# front_io.net
KiCad netlist of a schematic drawn in Altium Designer
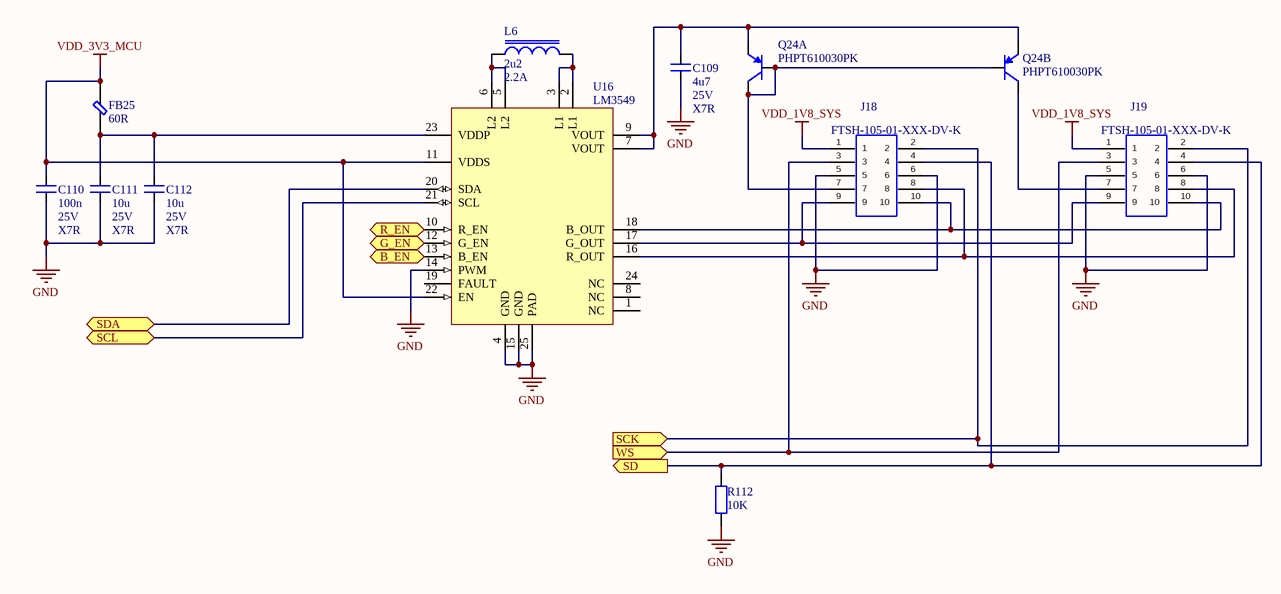
[diagram p0: front_io.SchDoc]

(export (version "E")
  (design (tool "Eeschema 10.0.6"))
  (components
    (comp (ref "C109")
      (value "4u7")
      (footprint "C3216[1206]")
      (description "Capacitor")
      (fields (field (name "VOLTAGE") "25V") (field (name "TYPE") "X7R") (field (name "Comment") "cap"))
      (libsource (lib "gpa_passives") (part "cap"))
    )
    (comp (ref "C110")
      (value "100n")
      (footprint "C1005[0402]")
      (description "Capacitor")
      (fields (field (name "VOLTAGE") "25V") (field (name "TYPE") "X7R") (field (name "Comment") "cap"))
      (libsource (lib "gpa_passives") (part "cap"))
    )
    (comp (ref "C111")
      (value "10u")
      (footprint "C3216[1206]")
      (description "Capacitor")
      (fields (field (name "VOLTAGE") "25V") (field (name "TYPE") "X7R") (field (name "Comment") "cap"))
      (libsource (lib "gpa_passives") (part "cap"))
    )
    (comp (ref "C112")
      (value "10u")
      (footprint "C3216[1206]")
      (description "Capacitor")
      (fields (field (name "VOLTAGE") "25V") (field (name "TYPE") "X7R") (field (name "Comment") "cap"))
      (libsource (lib "gpa_passives") (part "cap"))
    )
    (comp (ref "FB25")
      (value "60R")
      (footprint "FBC1608X07N")
      (description "Ferrite bead")
      (libsource (lib "gpa_passives") (part "ferrite_bead"))
    )
    (comp (ref "J18")
      (value "FTSH-105-01-XXX-DV-K")
      (footprint "FTSH-105-01-XXX-DV-K")
      (description "TERMINAL STRIP, .050\"(1.27mm) PITCH, 10 PINS, KEYED")
      (fields (field (name "MANUFACTURER") "SAMTEC") (field (name "CREATED") "November 30, 2016 - Wendy Xin"))
      (libsource (lib "FTSH-105-01-XXX-DV-K") (part "FTSH-105-01-XXX-DV-K"))
    )
    (comp (ref "J19")
      (value "FTSH-105-01-XXX-DV-K")
      (footprint "FTSH-105-01-XXX-DV-K")
      (description "TERMINAL STRIP, .050\"(1.27mm) PITCH, 10 PINS, KEYED")
      (fields (field (name "MANUFACTURER") "SAMTEC") (field (name "CREATED") "November 30, 2016 - Wendy Xin"))
      (libsource (lib "FTSH-105-01-XXX-DV-K") (part "FTSH-105-01-XXX-DV-K"))
    )
    (comp (ref "L6")
      (value "2u2")
      (footprint "YUDEN_NRS4018T-XXXMDGJ")
      (fields (field (name "CURRENT") "2.2A") (field (name "Comment") "ASPI-0630LR-XXXM-T15"))
      (libsource (lib "gpa_passives") (part "ind"))
    )
    (comp (ref "Q24")
      (value "PHPT610030PK")
      (footprint "NXP_LFPAK56D127P610X105-8N")
      (description "PNP Bipolar Transistor")
      (fields (field (name "PUBLISHER") "Altium Limited"))
      (libsource (lib "gpa_actives") (part "pnp_bipolar_dual"))
    )
    (comp (ref "R112")
      (value "10K")
      (footprint "R1005[0402]")
      (description "Resistor")
      (fields (field (name "TOLERANCE") "5%") (field (name "Comment") "res"))
      (libsource (lib "gpa_passives") (part "res"))
    )
    (comp (ref "U16")
      (value "LM3549")
      (footprint "TI_QFN50P400X400X80_HS-25M")
      (libsource (lib "gpa_ti") (part "lm3549"))
    )
  )
  (nets
    (net (code "1") (name "/B_EN") (class "Default")
      (node (ref "U16") (pin "13") (pinfunction "B_EN_13") (pintype "input"))
    )
    (net (code "2") (name "/G_EN") (class "Default")
      (node (ref "U16") (pin "12") (pinfunction "G_EN_12") (pintype "input"))
    )
    (net (code "3") (name "/R_EN") (class "Default")
      (node (ref "U16") (pin "10") (pinfunction "R_EN_10") (pintype "input"))
    )
    (net (code "4") (name "/SCK") (class "Default")
      (node (ref "J18") (pin "2") (pinfunction "2_2") (pintype "passive"))
      (node (ref "J19") (pin "2") (pinfunction "2_2") (pintype "passive"))
    )
    (net (code "5") (name "/SCL") (class "Default")
      (node (ref "U16") (pin "21") (pinfunction "SCL_21") (pintype "bidirectional"))
    )
    (net (code "6") (name "/SD") (class "Default")
      (node (ref "J18") (pin "4") (pinfunction "4_4") (pintype "passive"))
      (node (ref "J19") (pin "4") (pinfunction "4_4") (pintype "passive"))
      (node (ref "R112") (pin "2") (pinfunction "2_2") (pintype "passive"))
    )
    (net (code "7") (name "/SDA") (class "Default")
      (node (ref "U16") (pin "20") (pinfunction "SDA_20") (pintype "bidirectional"))
    )
    (net (code "8") (name "/WS") (class "Default")
      (node (ref "J18") (pin "3") (pinfunction "3_3") (pintype "passive"))
      (node (ref "J19") (pin "3") (pinfunction "3_3") (pintype "passive"))
    )
    (net (code "9") (name "GND") (class "Default")
      (node (ref "C109") (pin "1") (pinfunction "1_1") (pintype "passive"))
      (node (ref "C110") (pin "1") (pinfunction "1_1") (pintype "passive"))
      (node (ref "C111") (pin "1") (pinfunction "1_1") (pintype "passive"))
      (node (ref "C112") (pin "1") (pinfunction "1_1") (pintype "passive"))
      (node (ref "J18") (pin "5") (pinfunction "5_5") (pintype "passive"))
      (node (ref "J18") (pin "6") (pinfunction "6_6") (pintype "passive"))
      (node (ref "J19") (pin "5") (pinfunction "5_5") (pintype "passive"))
      (node (ref "J19") (pin "6") (pinfunction "6_6") (pintype "passive"))
      (node (ref "R112") (pin "1") (pinfunction "1_1") (pintype "passive"))
      (node (ref "U16") (pin "14") (pinfunction "PWM_14") (pintype "input"))
      (node (ref "U16") (pin "15") (pinfunction "GND_15") (pintype "power_in"))
      (node (ref "U16") (pin "25") (pinfunction "PAD_25") (pintype "power_in"))
      (node (ref "U16") (pin "4") (pinfunction "GND_4") (pintype "power_in"))
    )
    (net (code "10") (name "Net-(C109-Pad2)") (class "Default")
      (node (ref "C109") (pin "2") (pinfunction "2_2") (pintype "passive"))
      (node (ref "Q24") (pin "E1") (pinfunction "E1_E1") (pintype "passive"))
      (node (ref "Q24") (pin "E2") (pinfunction "E2_E2") (pintype "passive"))
      (node (ref "U16") (pin "7") (pinfunction "VOUT_7") (pintype "power_in"))
      (node (ref "U16") (pin "9") (pinfunction "VOUT_9") (pintype "power_in"))
    )
    (net (code "11") (name "Net-(J18-Pad7)") (class "Default")
      (node (ref "J18") (pin "7") (pinfunction "7_7") (pintype "passive"))
      (node (ref "Q24") (pin "B1") (pinfunction "B1_B1") (pintype "passive"))
      (node (ref "Q24") (pin "B2") (pinfunction "B2_B2") (pintype "passive"))
      (node (ref "Q24") (pin "C1") (pinfunction "C1_C1") (pintype "passive"))
    )
    (net (code "12") (name "Net-(J19-Pad7)") (class "Default")
      (node (ref "J19") (pin "7") (pinfunction "7_7") (pintype "passive"))
      (node (ref "Q24") (pin "C2") (pinfunction "C2_C2") (pintype "passive"))
    )
    (net (code "13") (name "Net-(L6-Pad1)") (class "Default")
      (node (ref "L6") (pin "1") (pinfunction "1_1") (pintype "passive"))
      (node (ref "U16") (pin "5") (pinfunction "L2_5") (pintype "power_in"))
      (node (ref "U16") (pin "6") (pinfunction "L2_6") (pintype "power_in"))
    )
    (net (code "14") (name "Net-(L6-Pad2)") (class "Default")
      (node (ref "L6") (pin "2") (pinfunction "2_2") (pintype "passive"))
      (node (ref "U16") (pin "2") (pinfunction "L1_2") (pintype "power_in"))
      (node (ref "U16") (pin "3") (pinfunction "L1_3") (pintype "power_in"))
    )
    (net (code "15") (name "Net-(U16-B_OUT)") (class "Default")
      (node (ref "J18") (pin "10") (pinfunction "10_10") (pintype "passive"))
      (node (ref "J19") (pin "10") (pinfunction "10_10") (pintype "passive"))
      (node (ref "U16") (pin "18") (pinfunction "B_OUT_18") (pintype "open_emitter"))
    )
    (net (code "16") (name "Net-(U16-G_OUT)") (class "Default")
      (node (ref "J18") (pin "9") (pinfunction "9_9") (pintype "passive"))
      (node (ref "J19") (pin "9") (pinfunction "9_9") (pintype "passive"))
      (node (ref "U16") (pin "17") (pinfunction "G_OUT_17") (pintype "open_emitter"))
    )
    (net (code "17") (name "Net-(U16-R_OUT)") (class "Default")
      (node (ref "J18") (pin "8") (pinfunction "8_8") (pintype "passive"))
      (node (ref "J19") (pin "8") (pinfunction "8_8") (pintype "passive"))
      (node (ref "U16") (pin "16") (pinfunction "R_OUT_16") (pintype "open_emitter"))
    )
    (net (code "18") (name "Net-(U16-VDDP)") (class "Default")
      (node (ref "C111") (pin "2") (pinfunction "2_2") (pintype "passive"))
      (node (ref "C112") (pin "2") (pinfunction "2_2") (pintype "passive"))
      (node (ref "FB25") (pin "1") (pinfunction "1_1") (pintype "passive"))
      (node (ref "U16") (pin "23") (pinfunction "VDDP_23") (pintype "power_in"))
    )
    (net (code "19") (name "VDD_1V8_SYS") (class "Default")
      (node (ref "J18") (pin "1") (pinfunction "1_1") (pintype "passive"))
      (node (ref "J19") (pin "1") (pinfunction "1_1") (pintype "passive"))
    )
    (net (code "20") (name "VDD_3V3_MCU") (class "Default")
      (node (ref "C110") (pin "2") (pinfunction "2_2") (pintype "passive"))
      (node (ref "FB25") (pin "2") (pinfunction "2_2") (pintype "passive"))
      (node (ref "U16") (pin "11") (pinfunction "VDDS_11") (pintype "power_in"))
      (node (ref "U16") (pin "22") (pinfunction "EN_22") (pintype "input"))
    )
    (net (code "21") (name "unconnected-(U16-FAULT-Pad19)") (class "Default")
      (node (ref "U16") (pin "19") (pinfunction "FAULT_19") (pintype "open_collector"))
    )
    (net (code "22") (name "unconnected-(U16-NC-Pad1)") (class "Default")
      (node (ref "U16") (pin "1") (pinfunction "NC_1") (pintype "passive"))
    )
    (net (code "23") (name "unconnected-(U16-NC-Pad8)") (class "Default")
      (node (ref "U16") (pin "8") (pinfunction "NC_8") (pintype "passive"))
    )
    (net (code "24") (name "unconnected-(U16-NC-Pad24)") (class "Default")
      (node (ref "U16") (pin "24") (pinfunction "NC_24") (pintype "passive"))
    )
  )
)
